# SCH_E-ink-smart-alarm-clock_2025-11-20.net
KiCad netlist of a schematic drawn in EasyEDA
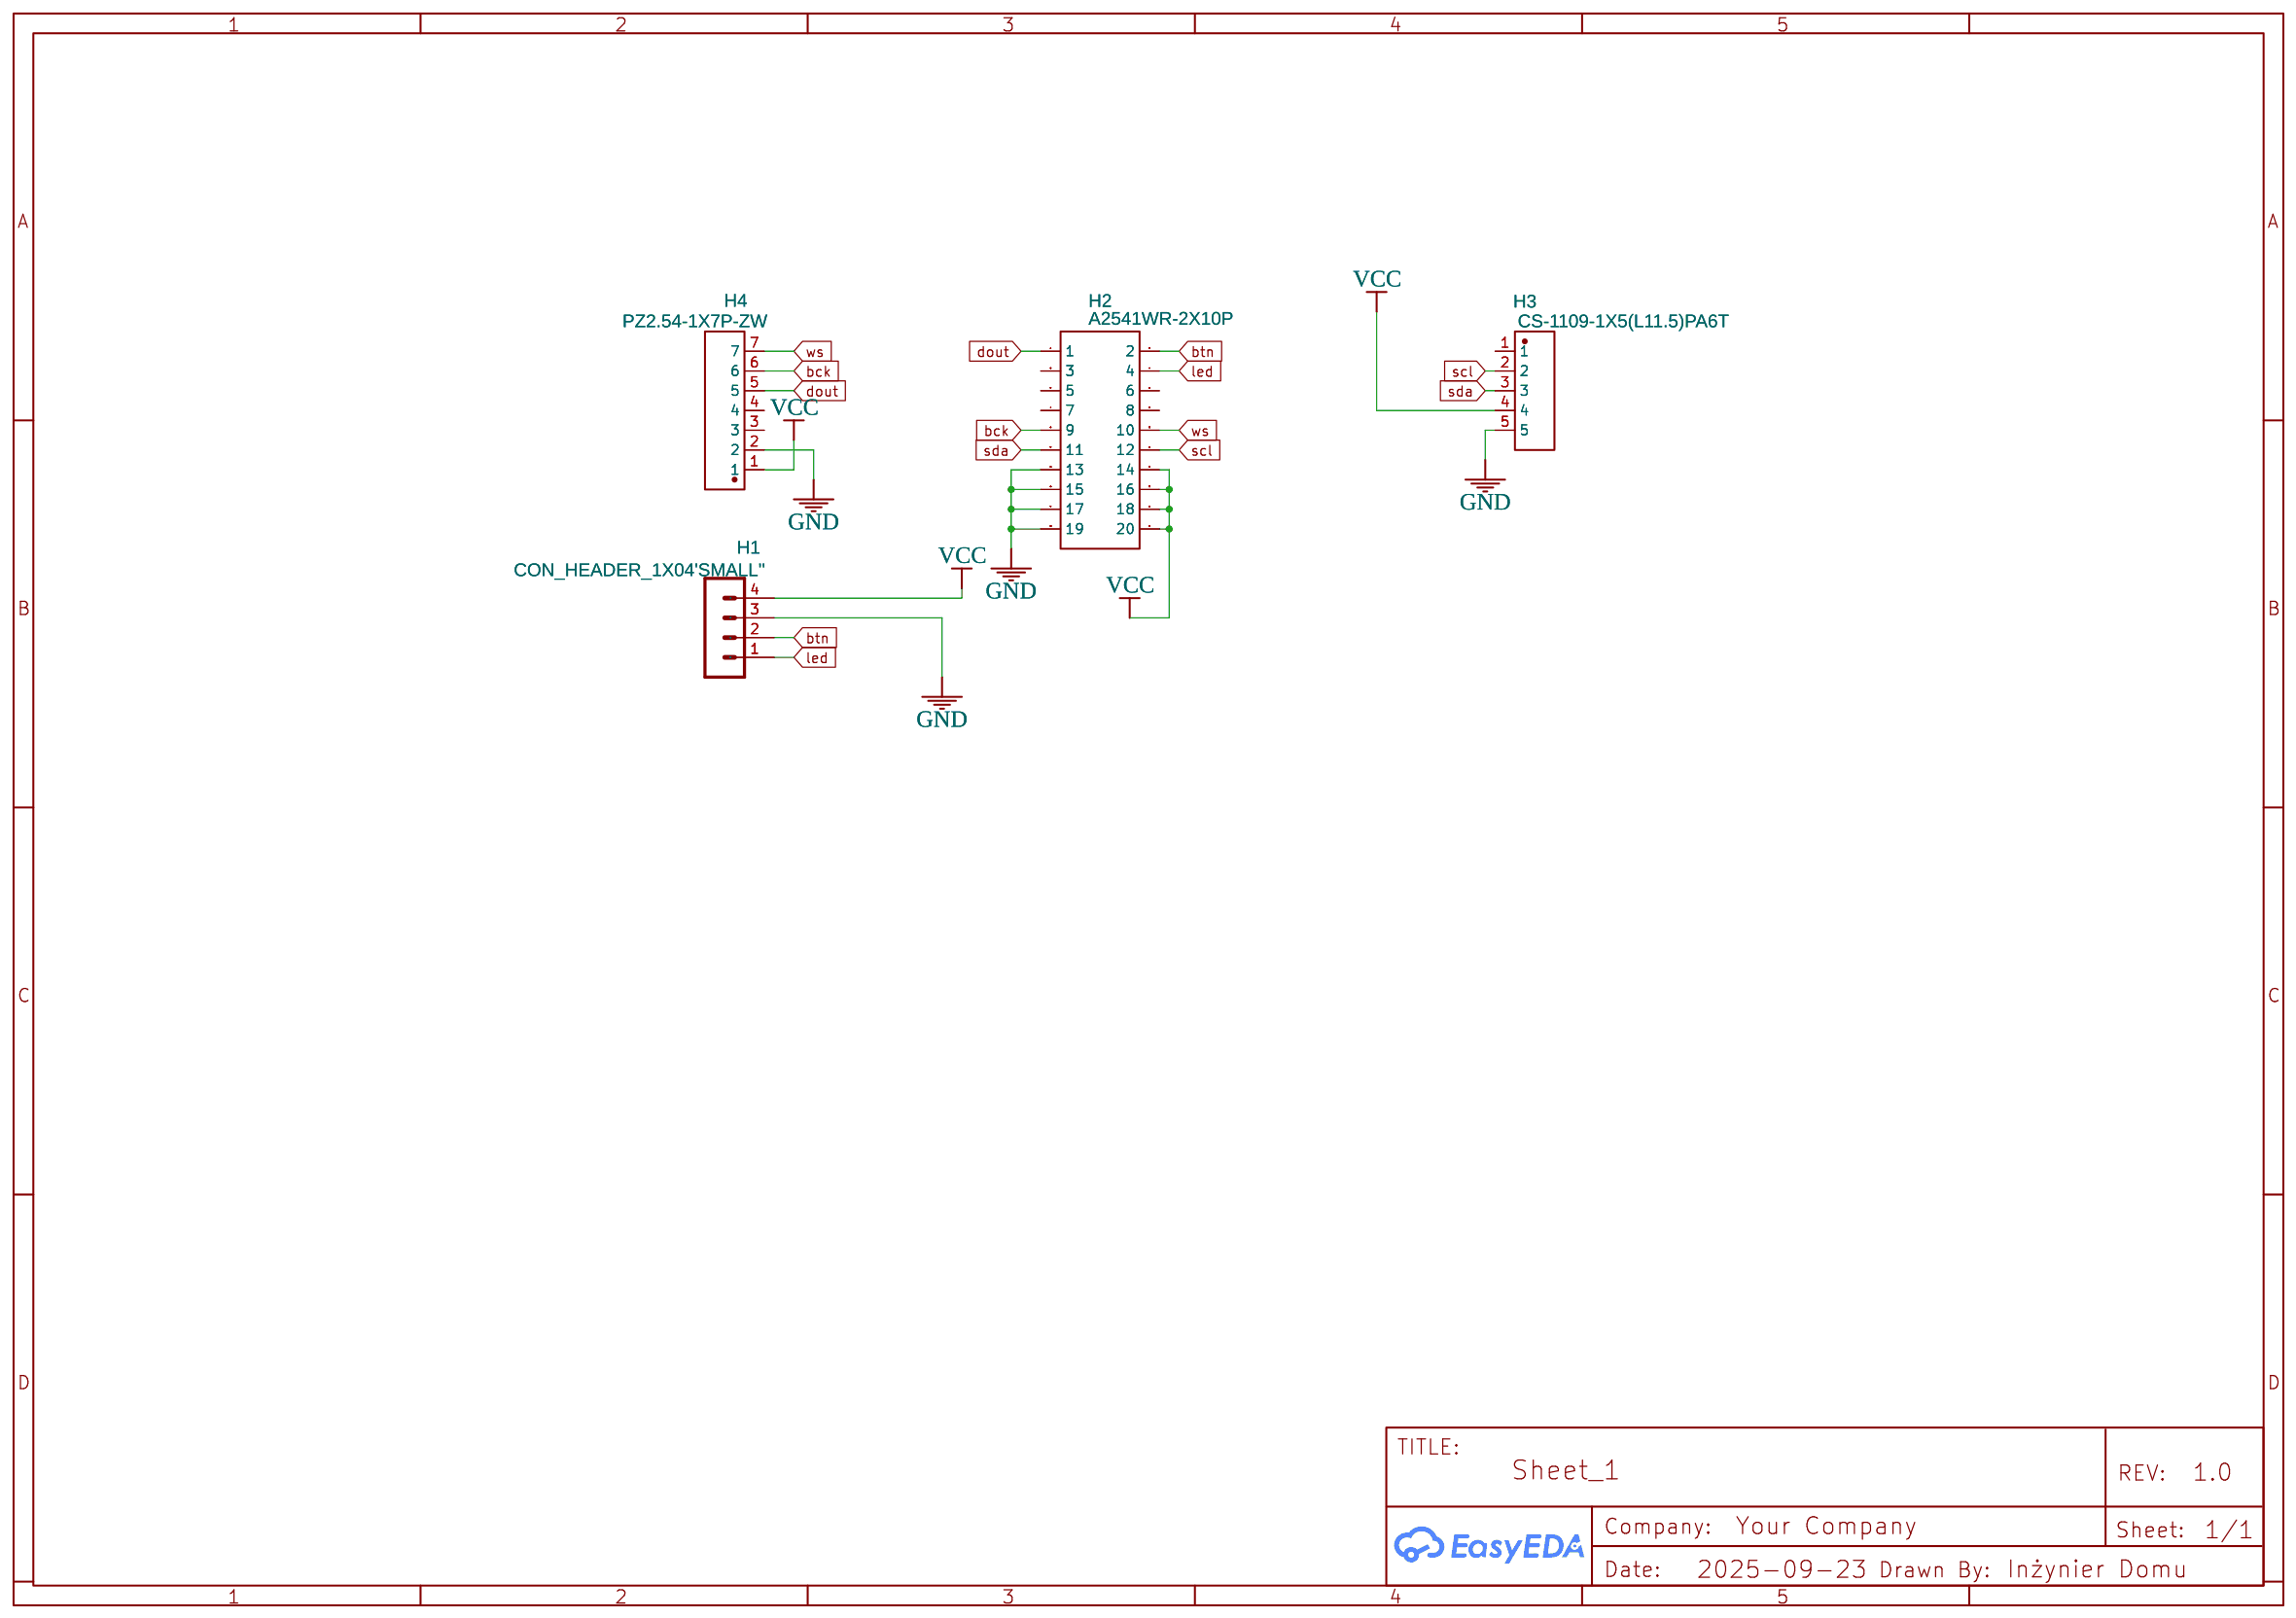
[diagram p0: schematic sheet]

(export (version "E")
  (design (tool "Eeschema 10.0.6"))
  (components
    (comp (ref "H1") (value "CON_HEADER_1X04'SMALL''") (libsource (lib "") (part "CON_HEADER_1X04'SMALL''")))
    (comp (ref "H2")
      (value "A2541WR-2X10P")
      (fields (field (name "Manufacturer Part") "A2541WR-2x10P") (field (name "Manufacturer") "CJT(长江连接器)"))
      (libsource (lib "") (part "A2541WR-2X10P"))
    )
    (comp (ref "H3")
      (value "CS-1109-1X5(L11.5)PA6T")
      (fields (field (name "Manufacturer") "CST(永丰盈)"))
      (libsource (lib "") (part "CS-1109-1X5(L11.5)PA6T"))
    )
    (comp (ref "H4") (value "PZ2.54-1X7P-ZW") (libsource (lib "") (part "PZ2.54-1X7P-ZW")))
  )
  (nets
    (net (code "1") (name "GND") (class "Default")
      (node (ref "H1") (pin "3") (pinfunction "3_3") (pintype "bidirectional"))
      (node (ref "H2") (pin "13") (pinfunction "13_13") (pintype "unspecified"))
      (node (ref "H2") (pin "15") (pinfunction "15_15") (pintype "unspecified"))
      (node (ref "H2") (pin "17") (pinfunction "17_17") (pintype "unspecified"))
      (node (ref "H2") (pin "19") (pinfunction "19_19") (pintype "unspecified"))
      (node (ref "H3") (pin "5") (pinfunction "5_5") (pintype "unspecified"))
      (node (ref "H4") (pin "2") (pinfunction "2_2") (pintype "unspecified"))
    )
    (net (code "2") (name "VCC") (class "Default")
      (node (ref "H1") (pin "4") (pinfunction "4_4") (pintype "bidirectional"))
      (node (ref "H2") (pin "14") (pinfunction "14_14") (pintype "unspecified"))
      (node (ref "H2") (pin "16") (pinfunction "16_16") (pintype "unspecified"))
      (node (ref "H2") (pin "18") (pinfunction "18_18") (pintype "unspecified"))
      (node (ref "H2") (pin "20") (pinfunction "20_20") (pintype "unspecified"))
      (node (ref "H3") (pin "4") (pinfunction "4_4") (pintype "unspecified"))
      (node (ref "H4") (pin "1") (pinfunction "1_1") (pintype "unspecified"))
    )
    (net (code "3") (name "bck") (class "Default")
      (node (ref "H2") (pin "9") (pinfunction "9_9") (pintype "unspecified"))
      (node (ref "H4") (pin "6") (pinfunction "6_6") (pintype "unspecified"))
    )
    (net (code "4") (name "btn") (class "Default")
      (node (ref "H1") (pin "2") (pinfunction "2_2") (pintype "bidirectional"))
      (node (ref "H2") (pin "2") (pinfunction "2_2") (pintype "unspecified"))
    )
    (net (code "5") (name "dout") (class "Default")
      (node (ref "H2") (pin "1") (pinfunction "1_1") (pintype "unspecified"))
      (node (ref "H4") (pin "5") (pinfunction "5_5") (pintype "unspecified"))
    )
    (net (code "6") (name "led") (class "Default")
      (node (ref "H1") (pin "1") (pinfunction "1_1") (pintype "bidirectional"))
      (node (ref "H2") (pin "4") (pinfunction "4_4") (pintype "unspecified"))
    )
    (net (code "7") (name "scl") (class "Default")
      (node (ref "H2") (pin "12") (pinfunction "12_12") (pintype "unspecified"))
      (node (ref "H3") (pin "2") (pinfunction "2_2") (pintype "unspecified"))
    )
    (net (code "8") (name "sda") (class "Default")
      (node (ref "H2") (pin "11") (pinfunction "11_11") (pintype "unspecified"))
      (node (ref "H3") (pin "3") (pinfunction "3_3") (pintype "unspecified"))
    )
    (net (code "9") (name "unconnected-(H2-Pad3)") (class "Default")
      (node (ref "H2") (pin "3") (pinfunction "3_3") (pintype "unspecified"))
    )
    (net (code "10") (name "unconnected-(H2-Pad5)") (class "Default")
      (node (ref "H2") (pin "5") (pinfunction "5_5") (pintype "unspecified"))
    )
    (net (code "11") (name "unconnected-(H2-Pad6)") (class "Default")
      (node (ref "H2") (pin "6") (pinfunction "6_6") (pintype "unspecified"))
    )
    (net (code "12") (name "unconnected-(H2-Pad7)") (class "Default")
      (node (ref "H2") (pin "7") (pinfunction "7_7") (pintype "unspecified"))
    )
    (net (code "13") (name "unconnected-(H2-Pad8)") (class "Default")
      (node (ref "H2") (pin "8") (pinfunction "8_8") (pintype "unspecified"))
    )
    (net (code "14") (name "unconnected-(H3-Pad1)") (class "Default")
      (node (ref "H3") (pin "1") (pinfunction "1_1") (pintype "unspecified"))
    )
    (net (code "15") (name "unconnected-(H4-Pad3)") (class "Default")
      (node (ref "H4") (pin "3") (pinfunction "3_3") (pintype "unspecified"))
    )
    (net (code "16") (name "unconnected-(H4-Pad4)") (class "Default")
      (node (ref "H4") (pin "4") (pinfunction "4_4") (pintype "unspecified"))
    )
    (net (code "17") (name "ws") (class "Default")
      (node (ref "H2") (pin "10") (pinfunction "10_10") (pintype "unspecified"))
      (node (ref "H4") (pin "7") (pinfunction "7_7") (pintype "unspecified"))
    )
  )
)
